# Canzasi-Wrtr.net
KiCad netlist of a schematic drawn in EAGLE
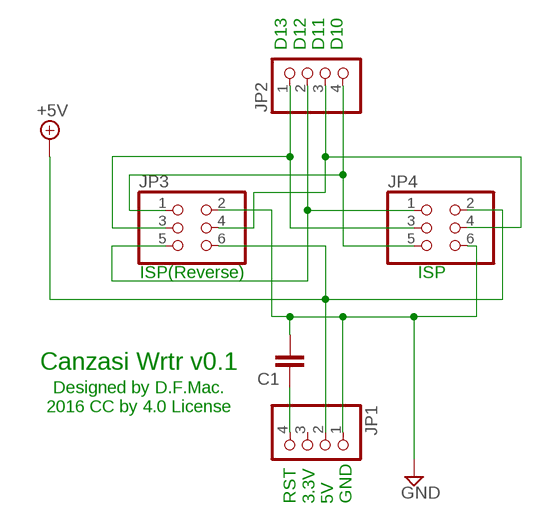
[diagram p0: schematic, sheet 1]

(export (version "E")
  (design (tool "Eeschema 10.0.6"))
  (components
    (comp (ref "C1")
      (value "C-EUC0805")
      (footprint "eagle-import:C0805")
      (libsource (lib "eagle-import") (part "C-EUC0805"))
    )
    (comp (ref "JP1")
      (value "PINHD-1X4")
      (footprint "eagle-import:1X04")
      (libsource (lib "eagle-import") (part "PINHD-1X4"))
    )
    (comp (ref "JP2")
      (value "PINHD-1X4")
      (footprint "eagle-import:1X04")
      (libsource (lib "eagle-import") (part "PINHD-1X4"))
    )
    (comp (ref "JP3")
      (value "PINHD-2X3")
      (footprint "eagle-import:2X03")
      (libsource (lib "eagle-import") (part "PINHD-2X3"))
    )
    (comp (ref "JP4")
      (value "PINHD-2X3")
      (footprint "eagle-import:2X03")
      (libsource (lib "eagle-import") (part "PINHD-2X3"))
    )
  )
  (nets
    (net (code "1") (name "+5V") (class "Default")
      (node (ref "JP1") (pin "2") (pinfunction "2_2") (pintype "passive"))
      (node (ref "JP3") (pin "6") (pinfunction "6_6") (pintype "passive"))
      (node (ref "JP4") (pin "2") (pinfunction "2_2") (pintype "passive"))
    )
    (net (code "2") (name "GND") (class "Default")
      (node (ref "C1") (pin "2") (pinfunction "2_2") (pintype "passive"))
      (node (ref "JP1") (pin "1") (pinfunction "1_1") (pintype "passive"))
      (node (ref "JP3") (pin "2") (pinfunction "2_2") (pintype "passive"))
      (node (ref "JP4") (pin "6") (pinfunction "6_6") (pintype "passive"))
    )
    (net (code "3") (name "Net-(C1-Pad1)") (class "Default")
      (node (ref "C1") (pin "1") (pinfunction "1_1") (pintype "passive"))
      (node (ref "JP1") (pin "4") (pinfunction "4_4") (pintype "passive"))
    )
    (net (code "4") (name "Net-(JP2-Pad1)") (class "Default")
      (node (ref "JP2") (pin "1") (pinfunction "1_1") (pintype "passive"))
      (node (ref "JP3") (pin "3") (pinfunction "3_3") (pintype "passive"))
      (node (ref "JP4") (pin "3") (pinfunction "3_3") (pintype "passive"))
    )
    (net (code "5") (name "Net-(JP2-Pad2)") (class "Default")
      (node (ref "JP2") (pin "2") (pinfunction "2_2") (pintype "passive"))
      (node (ref "JP3") (pin "5") (pinfunction "5_5") (pintype "passive"))
      (node (ref "JP4") (pin "1") (pinfunction "1_1") (pintype "passive"))
    )
    (net (code "6") (name "Net-(JP2-Pad3)") (class "Default")
      (node (ref "JP2") (pin "3") (pinfunction "3_3") (pintype "passive"))
      (node (ref "JP3") (pin "4") (pinfunction "4_4") (pintype "passive"))
      (node (ref "JP4") (pin "4") (pinfunction "4_4") (pintype "passive"))
    )
    (net (code "7") (name "Net-(JP2-Pad4)") (class "Default")
      (node (ref "JP2") (pin "4") (pinfunction "4_4") (pintype "passive"))
      (node (ref "JP3") (pin "1") (pinfunction "1_1") (pintype "passive"))
      (node (ref "JP4") (pin "5") (pinfunction "5_5") (pintype "passive"))
    )
    (net (code "8") (name "unconnected-(JP1-Pad3)") (class "Default")
      (node (ref "JP1") (pin "3") (pinfunction "3_3") (pintype "passive"))
    )
  )
)
